# MD070B_DRIVER.net
KiCad netlist of a schematic drawn in Altium Designer
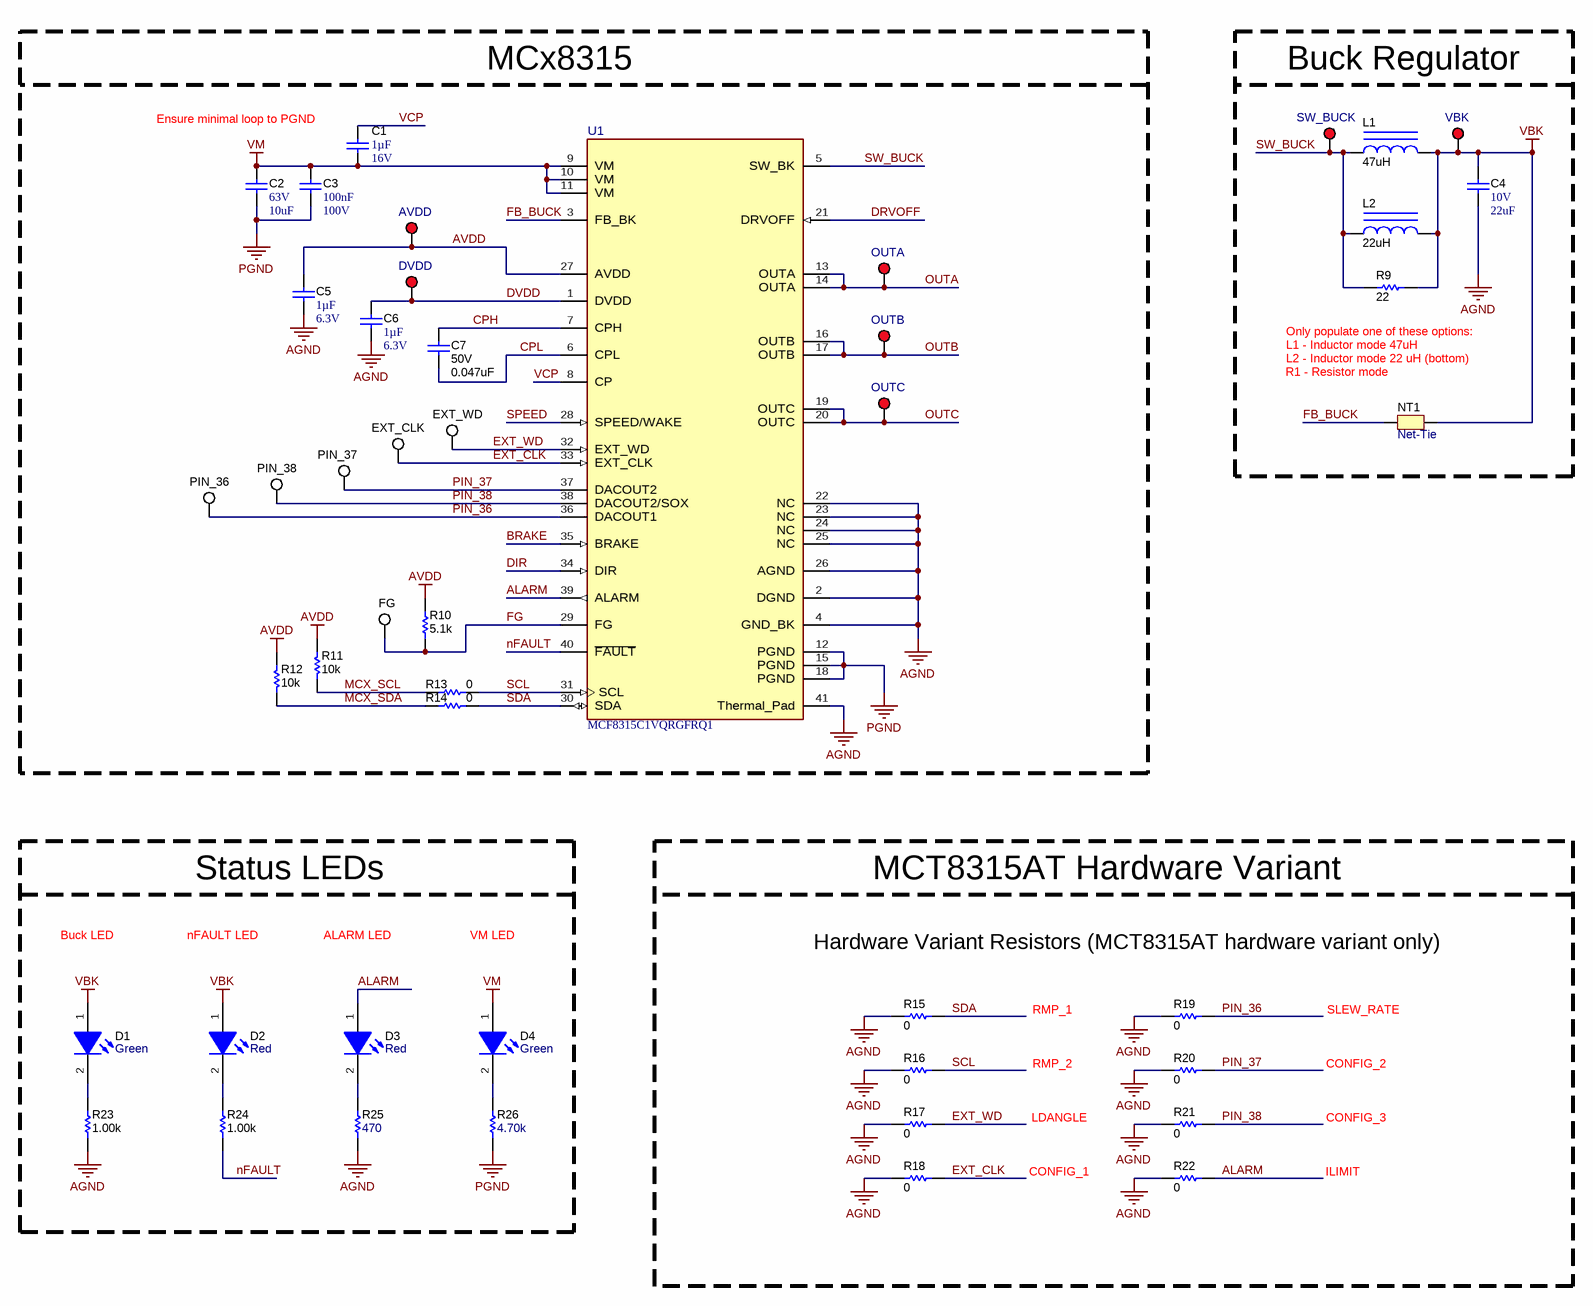
[diagram p0: MD070B_DRIVER.SchDoc]

(export (version "E")
  (design (tool "Eeschema 10.0.6"))
  (components
    (comp (ref "C1")
      (value "EMK107B7105KAHT")
      (footprint "0603L")
      (description "CAP, CERM, 1 µF, 16 V,+/- 10%, X7R, AEC-Q200 Grade 1, 0603")
      (fields
        (field (name "CAP_F") "1µF")
        (field (name "MANUFACTURER") "Taiyo Yuden")
        (field (name "VDC_V") "16V")
      )
      (libsource (lib "Altium Vault - TI") (part "Capacitor"))
    )
    (comp (ref "C2")
      (value "GRM32ER71J106KA12L")
      (footprint "1210_270L")
      (description "CAP, CERM, 10 uF, 63 V, +/- 10%, X7R, 1210")
      (fields
        (field (name "MANUFACTURER") "MuRata")
        (field (name "VDC_V") "63V")
        (field (name "VALUEDISPLAYED") "10uF")
        (field (name "PUBLISHER") "Texas Instruments")
      )
      (libsource (lib "Altium Vault - TI") (part "Capacitor"))
    )
    (comp (ref "C3")
      (value "GRM188R72A104KA35D")
      (footprint "0603")
      (description "CAP, CERM, 0.1 uF, 100 V, +/- 10%, X7R, 0603")
      (fields
        (field (name "CAP_F") "100nF")
        (field (name "MANUFACTURER") "MuRata")
        (field (name "VDC_V") "100V")
        (field (name "PUBLISHER") "Texas Instruments")
      )
      (libsource (lib "Altium Vault - TI") (part "Capacitor"))
    )
    (comp (ref "C4")
      (value "GRM31CR71A226KE15L")
      (footprint "1206_180L")
      (description "CAP, CERM, 22 uF, 10 V, +/- 10%, X7R, 1206")
      (fields
        (field (name "MANUFACTURER") "MuRata")
        (field (name "VDC_V") "10V")
        (field (name "VALUEDISPLAYED") "22uF")
        (field (name "PUBLISHER") "Texas Instruments")
      )
      (libsource (lib "Altium Vault - TI") (part "Capacitor"))
    )
    (comp (ref "C5")
      (value "C0603C105K9RACAUTO")
      (footprint "0603L")
      (description "CAP, CERM, 1 µF, 6.3 V,+/- 10%, X7R, AEC-Q200 Grade 1, 0603")
      (fields
        (field (name "CAP_F") "1µF")
        (field (name "MANUFACTURER") "Kemet")
        (field (name "VDC_V") "6.3V")
      )
      (libsource (lib "Altium Vault - TI") (part "Capacitor"))
    )
    (comp (ref "C6")
      (value "C0603C105K9RACAUTO")
      (footprint "0603L")
      (description "CAP, CERM, 1 µF, 6.3 V,+/- 10%, X7R, AEC-Q200 Grade 1, 0603")
      (fields
        (field (name "CAP_F") "1µF")
        (field (name "MANUFACTURER") "Kemet")
        (field (name "VDC_V") "6.3V")
      )
      (libsource (lib "Altium Vault - TI") (part "Capacitor"))
    )
    (comp (ref "C7")
      (value "C1005X7R1H473K050BB")
      (footprint "0402L")
      (description "CAP, CERM, 0.047 uF, 50 V, +/- 10%, X7R, 0402")
      (fields
        (field (name "MANUFACTURER") "TDK")
        (field (name "VDC_V") "50V")
        (field (name "VALUEDISPLAYED") "0.047uF")
        (field (name "PUBLISHER") "Texas Instruments")
      )
      (libsource (lib "Altium Vault - TI") (part "Capacitor"))
    )
    (comp (ref "D1")
      (value "Green")
      (footprint "LTST-C170KGKT_Green")
      (description "LED, Green, SMD")
      (fields (field (name "MANUFACTURER") "Lite-On") (field (name "PARTNUMBER") "LTST-C170KGKT"))
      (libsource (lib "Altium Vault - TI") (part "LED"))
    )
    (comp (ref "D2")
      (value "Red")
      (footprint "LED_LTST-C170_Red")
      (description "LED, Red, SMD")
      (fields (field (name "MANUFACTURER") "Lite-On") (field (name "PARTNUMBER") "LTST-C170KRKT"))
      (libsource (lib "Altium Vault - TI") (part "LED"))
    )
    (comp (ref "D3")
      (value "Red")
      (footprint "LED_LTST-C170_Red")
      (description "LED, Red, SMD")
      (fields (field (name "MANUFACTURER") "Lite-On") (field (name "PARTNUMBER") "LTST-C170KRKT"))
      (libsource (lib "Altium Vault - TI") (part "LED"))
    )
    (comp (ref "D4")
      (value "Green")
      (footprint "LTST-C170KGKT_Green")
      (description "LED, Green, SMD")
      (fields (field (name "MANUFACTURER") "Lite-On") (field (name "PARTNUMBER") "LTST-C170KGKT"))
      (libsource (lib "Altium Vault - TI") (part "LED"))
    )
    (comp (ref "L1")
      (value "78438335470")
      (footprint "WE-MAIA_3015")
      (description "Inductor, Shielded, Powdered Iron, 47 uH, 0.39 A, 2.3 ohm, AEC-Q200 Grade 1, SMD")
      (fields
        (field (name "MANUFACTURER") "Wurth Elektronik")
        (field (name "VALUEDISPLAYED") "47uH")
        (field (name "PUBLISHER") "Texas Instruments")
      )
      (libsource (lib "Altium Vault - TI") (part "Inductor_Iron"))
    )
    (comp (ref "L2")
      (value "78438335220")
      (footprint "WE-MAIA_3015")
      (description "Inductor, Shielded, Powdered Iron, 22 uH, 0.6 A, 1.04 ohm, AEC-Q200 Grade 1, SMD")
      (fields
        (field (name "MANUFACTURER") "Wurth Elektronik")
        (field (name "VALUEDISPLAYED") "22uH")
        (field (name "PUBLISHER") "Texas Instruments")
      )
      (libsource (lib "Altium Vault - TI") (part "Inductor_Iron"))
    )
    (comp (ref "NT1")
      (value "Net-Tie")
      (footprint "Net-Tie_10mil")
      (description "Single point connection between nets.")
      (libsource (lib "Altium Vault - TI") (part "Net-Tie"))
    )
    (comp (ref "R9")
      (value "CRCW251222R0JNEGHP")
      (footprint "2512")
      (description "RES, 22, 5%, 1.5 W, AEC-Q200 Grade 0, 2512")
      (fields (field (name "MANUFACTURER") "Vishay-Dale") (field (name "VALUEDISPLAYED") "22"))
      (libsource (lib "Altium Vault - TI") (part "Resistor"))
    )
    (comp (ref "R10")
      (value "CRCW06035K10JNEA")
      (footprint "0603L")
      (description "RES, 5.1 k, 5%, 0.1 W, AEC-Q200 Grade 0, 0603")
      (fields (field (name "MANUFACTURER") "Vishay-Dale") (field (name "VALUEDISPLAYED") "5.1k"))
      (libsource (lib "Altium Vault - TI") (part "Resistor"))
    )
    (comp (ref "R11")
      (value "CRCW060310K0JNEA")
      (footprint "0603")
      (description "RES, 10 k, 5%, 0.1 W, AEC-Q200 Grade 0, 0603")
      (fields (field (name "MANUFACTURER") "Vishay-Dale") (field (name "VALUEDISPLAYED") "10k"))
      (libsource (lib "Altium Vault - TI") (part "Resistor"))
    )
    (comp (ref "R12")
      (value "CRCW060310K0JNEA")
      (footprint "0603")
      (description "RES, 10 k, 5%, 0.1 W, AEC-Q200 Grade 0, 0603")
      (fields (field (name "MANUFACTURER") "Vishay-Dale") (field (name "VALUEDISPLAYED") "10k"))
      (libsource (lib "Altium Vault - TI") (part "Resistor"))
    )
    (comp (ref "R13")
      (value "ERJ-3GEY0R00V")
      (footprint "0603L")
      (description "RES, 0, 5%, 0.1 W, AEC-Q200 Grade 0, 0603")
      (fields (field (name "MANUFACTURER") "Panasonic") (field (name "VALUEDISPLAYED") "0"))
      (libsource (lib "Altium Vault - TI") (part "Resistor"))
    )
    (comp (ref "R14")
      (value "ERJ-3GEY0R00V")
      (footprint "0603L")
      (description "RES, 0, 5%, 0.1 W, AEC-Q200 Grade 0, 0603")
      (fields (field (name "MANUFACTURER") "Panasonic") (field (name "VALUEDISPLAYED") "0"))
      (libsource (lib "Altium Vault - TI") (part "Resistor"))
    )
    (comp (ref "R15")
      (value "ERJ-3GEY0R00V")
      (footprint "0603L")
      (description "RES, 0, 5%, 0.1 W, AEC-Q200 Grade 0, 0603")
      (fields (field (name "MANUFACTURER") "Panasonic") (field (name "VALUEDISPLAYED") "0"))
      (libsource (lib "Altium Vault - TI") (part "Resistor"))
    )
    (comp (ref "R16")
      (value "ERJ-3GEY0R00V")
      (footprint "0603L")
      (description "RES, 0, 5%, 0.1 W, AEC-Q200 Grade 0, 0603")
      (fields (field (name "MANUFACTURER") "Panasonic") (field (name "VALUEDISPLAYED") "0"))
      (libsource (lib "Altium Vault - TI") (part "Resistor"))
    )
    (comp (ref "R17")
      (value "ERJ-3GEY0R00V")
      (footprint "0603L")
      (description "RES, 0, 5%, 0.1 W, AEC-Q200 Grade 0, 0603")
      (fields (field (name "MANUFACTURER") "Panasonic") (field (name "VALUEDISPLAYED") "0"))
      (libsource (lib "Altium Vault - TI") (part "Resistor"))
    )
    (comp (ref "R18")
      (value "ERJ-3GEY0R00V")
      (footprint "0603L")
      (description "RES, 0, 5%, 0.1 W, AEC-Q200 Grade 0, 0603")
      (fields (field (name "MANUFACTURER") "Panasonic") (field (name "VALUEDISPLAYED") "0"))
      (libsource (lib "Altium Vault - TI") (part "Resistor"))
    )
    (comp (ref "R19")
      (value "ERJ-3GEY0R00V")
      (footprint "0603L")
      (description "RES, 0, 5%, 0.1 W, AEC-Q200 Grade 0, 0603")
      (fields (field (name "MANUFACTURER") "Panasonic") (field (name "VALUEDISPLAYED") "0"))
      (libsource (lib "Altium Vault - TI") (part "Resistor"))
    )
    (comp (ref "R20")
      (value "ERJ-3GEY0R00V")
      (footprint "0603L")
      (description "RES, 0, 5%, 0.1 W, AEC-Q200 Grade 0, 0603")
      (fields (field (name "MANUFACTURER") "Panasonic") (field (name "VALUEDISPLAYED") "0"))
      (libsource (lib "Altium Vault - TI") (part "Resistor"))
    )
    (comp (ref "R21")
      (value "ERJ-3GEY0R00V")
      (footprint "0603L")
      (description "RES, 0, 5%, 0.1 W, AEC-Q200 Grade 0, 0603")
      (fields (field (name "MANUFACTURER") "Panasonic") (field (name "VALUEDISPLAYED") "0"))
      (libsource (lib "Altium Vault - TI") (part "Resistor"))
    )
    (comp (ref "R22")
      (value "ERJ-3GEY0R00V")
      (footprint "0603L")
      (description "RES, 0, 5%, 0.1 W, AEC-Q200 Grade 0, 0603")
      (fields (field (name "MANUFACTURER") "Panasonic") (field (name "VALUEDISPLAYED") "0"))
      (libsource (lib "Altium Vault - TI") (part "Resistor"))
    )
    (comp (ref "R23")
      (value "RC0603FR-071KL")
      (footprint "0603")
      (description "RES, 1.00 k, 1%, 0.1 W, 0603")
      (fields (field (name "MANUFACTURER") "Yageo") (field (name "VALUEDISPLAYED") "1.00k"))
      (libsource (lib "Altium Vault - TI") (part "Resistor"))
    )
    (comp (ref "R24")
      (value "RC0603FR-071KL")
      (footprint "0603")
      (description "RES, 1.00 k, 1%, 0.1 W, 0603")
      (fields (field (name "MANUFACTURER") "Yageo") (field (name "VALUEDISPLAYED") "1.00k"))
      (libsource (lib "Altium Vault - TI") (part "Resistor"))
    )
    (comp (ref "R25")
      (value "RC0603JR-07470RL")
      (footprint "0603")
      (description "RES, 470, 5%, 0.1 W, 0603")
      (fields (field (name "MANUFACTURER") "Yageo") (field (name "VALUEDISPLAYED") "470"))
      (libsource (lib "Altium Vault - TI") (part "Resistor"))
    )
    (comp (ref "R26")
      (value "RT0603BRD074K7L")
      (footprint "0603L")
      (description "RES, 4.70 k, 0.1%, 0.1 W, 0603")
      (fields
        (field (name "MANUFACTURER") "Yageo America")
        (field (name "VALUEDISPLAYED") "4.70k")
        (field (name "PUBLISHER") "Texas Instruments")
      )
      (libsource (lib "Altium Vault - TI") (part "Resistor"))
    )
    (comp (ref "TP5")
      (value "SW_BUCK")
      (footprint "Keystone5000")
      (description "Test Point, Miniature, Red, TH")
      (fields
        (field (name "PARTNUMBER") "5000")
        (field (name "MANUFACTURER") "Keystone")
        (field (name "PUBLISHER") "Texas Instruments")
      )
      (libsource (lib "Altium Vault - TI") (part "CMP-0055137-1"))
    )
    (comp (ref "TP6")
      (value "VBK")
      (footprint "Keystone5000")
      (description "Test Point, Miniature, Red, TH")
      (fields
        (field (name "PARTNUMBER") "5000")
        (field (name "MANUFACTURER") "Keystone")
        (field (name "PUBLISHER") "Texas Instruments")
      )
      (libsource (lib "Altium Vault - TI") (part "CMP-0055137-1"))
    )
    (comp (ref "TP7")
      (value "AVDD")
      (footprint "Keystone5000")
      (description "Test Point, Miniature, Red, TH")
      (fields
        (field (name "PARTNUMBER") "5000")
        (field (name "MANUFACTURER") "Keystone")
        (field (name "PUBLISHER") "Texas Instruments")
      )
      (libsource (lib "Altium Vault - TI") (part "CMP-0055137-1"))
    )
    (comp (ref "TP8")
      (value "DVDD")
      (footprint "Keystone5000")
      (description "Test Point, Miniature, Red, TH")
      (fields
        (field (name "PARTNUMBER") "5000")
        (field (name "MANUFACTURER") "Keystone")
        (field (name "PUBLISHER") "Texas Instruments")
      )
      (libsource (lib "Altium Vault - TI") (part "CMP-0055137-1"))
    )
    (comp (ref "TP9")
      (value "OUTA")
      (footprint "Keystone5000")
      (description "Test Point, Miniature, Red, TH")
      (fields
        (field (name "PARTNUMBER") "5000")
        (field (name "MANUFACTURER") "Keystone")
        (field (name "PUBLISHER") "Texas Instruments")
      )
      (libsource (lib "Altium Vault - TI") (part "CMP-0055137-1"))
    )
    (comp (ref "TP10")
      (value "OUTB")
      (footprint "Keystone5000")
      (description "Test Point, Miniature, Red, TH")
      (fields
        (field (name "PARTNUMBER") "5000")
        (field (name "MANUFACTURER") "Keystone")
        (field (name "PUBLISHER") "Texas Instruments")
      )
      (libsource (lib "Altium Vault - TI") (part "CMP-0055137-1"))
    )
    (comp (ref "TP11")
      (value "OUTC")
      (footprint "Keystone5000")
      (description "Test Point, Miniature, Red, TH")
      (fields
        (field (name "PARTNUMBER") "5000")
        (field (name "MANUFACTURER") "Keystone")
        (field (name "PUBLISHER") "Texas Instruments")
      )
      (libsource (lib "Altium Vault - TI") (part "CMP-0055137-1"))
    )
    (comp (ref "TP12")
      (value "EXT_WD")
      (footprint "Keystone5002")
      (description "Test Point, Miniature, White, TH")
      (fields
        (field (name "MANUFACTURER") "Keystone")
        (field (name "PARTNUMBER") "5002")
        (field (name "PUBLISHER") "Texas Instruments")
      )
      (libsource (lib "Altium Vault - TI") (part "5002"))
    )
    (comp (ref "TP13")
      (value "EXT_CLK")
      (footprint "Keystone5002")
      (description "Test Point, Miniature, White, TH")
      (fields
        (field (name "MANUFACTURER") "Keystone")
        (field (name "PARTNUMBER") "5002")
        (field (name "PUBLISHER") "Texas Instruments")
      )
      (libsource (lib "Altium Vault - TI") (part "5002"))
    )
    (comp (ref "TP14")
      (value "PIN_37")
      (footprint "Keystone5002")
      (description "Test Point, Miniature, White, TH")
      (fields
        (field (name "MANUFACTURER") "Keystone")
        (field (name "PARTNUMBER") "5002")
        (field (name "PUBLISHER") "Texas Instruments")
      )
      (libsource (lib "Altium Vault - TI") (part "5002"))
    )
    (comp (ref "TP15")
      (value "PIN_38")
      (footprint "Keystone5002")
      (description "Test Point, Miniature, White, TH")
      (fields
        (field (name "MANUFACTURER") "Keystone")
        (field (name "PARTNUMBER") "5002")
        (field (name "PUBLISHER") "Texas Instruments")
      )
      (libsource (lib "Altium Vault - TI") (part "5002"))
    )
    (comp (ref "TP16")
      (value "PIN_36")
      (footprint "Keystone5002")
      (description "Test Point, Miniature, White, TH")
      (fields
        (field (name "MANUFACTURER") "Keystone")
        (field (name "PARTNUMBER") "5002")
        (field (name "PUBLISHER") "Texas Instruments")
      )
      (libsource (lib "Altium Vault - TI") (part "5002"))
    )
    (comp (ref "TP17")
      (value "FG")
      (footprint "Keystone5002")
      (description "Test Point, Miniature, White, TH")
      (fields
        (field (name "MANUFACTURER") "Keystone")
        (field (name "PARTNUMBER") "5002")
        (field (name "PUBLISHER") "Texas Instruments")
      )
      (libsource (lib "Altium Vault - TI") (part "5002"))
    )
    (comp (ref "U1")
      (value "MCF8315C1VQRGFRQ1")
      (footprint "RGF0040F-MFG")
      (description "Sensorless Field Oriented Control (FOC) Integrated FET BLDC Driver")
      (fields
        (field (name "MANUFACTURER") "Texas Instruments")
        (field (name "PARTNUMBER") "MCF8315C1VQRGFRQ1")
        (field (name "DIGIKEY PART NUMBER") "296-MCF8315C1VQRGFRQ1CT-ND")
      )
      (libsource (lib "Altium Vault - TI") (part "SYM-MCF8315C1VQRGFRQ1"))
    )
  )
  (nets
    (net (code "1") (name "/ALARM") (class "Default")
      (node (ref "D3") (pin "1") (pinfunction "A_1") (pintype "passive"))
      (node (ref "R22") (pin "1") (pinfunction "1_1") (pintype "passive"))
      (node (ref "U1") (pin "39") (pinfunction "ALARM_39") (pintype "output"))
    )
    (net (code "2") (name "/BRAKE") (class "Default")
      (node (ref "U1") (pin "35") (pinfunction "BRAKE_35") (pintype "input"))
    )
    (net (code "3") (name "/CPH") (class "Default")
      (node (ref "C7") (pin "1") (pinfunction "1_1") (pintype "passive"))
      (node (ref "U1") (pin "7") (pinfunction "CPH_7") (pintype "passive"))
    )
    (net (code "4") (name "/CPL") (class "Default")
      (node (ref "C7") (pin "2") (pinfunction "2_2") (pintype "passive"))
      (node (ref "U1") (pin "6") (pinfunction "CPL_6") (pintype "passive"))
    )
    (net (code "5") (name "/DIR") (class "Default")
      (node (ref "U1") (pin "34") (pinfunction "DIR_34") (pintype "input"))
    )
    (net (code "6") (name "/DRVOFF") (class "Default")
      (node (ref "U1") (pin "21") (pinfunction "DRVOFF_21") (pintype "input"))
    )
    (net (code "7") (name "/DVDD") (class "Default")
      (node (ref "C6") (pin "2") (pinfunction "2_2") (pintype "passive"))
      (node (ref "TP8") (pin "1") (pintype "passive"))
      (node (ref "U1") (pin "1") (pinfunction "DVDD_1") (pintype "power_in"))
    )
    (net (code "8") (name "/EXT_CLK") (class "Default")
      (node (ref "R18") (pin "1") (pinfunction "1_1") (pintype "passive"))
      (node (ref "TP13") (pin "1") (pintype "passive"))
      (node (ref "U1") (pin "33") (pinfunction "EXT_CLK_33") (pintype "input"))
    )
    (net (code "9") (name "/EXT_WD") (class "Default")
      (node (ref "R17") (pin "1") (pinfunction "1_1") (pintype "passive"))
      (node (ref "TP12") (pin "1") (pintype "passive"))
      (node (ref "U1") (pin "32") (pinfunction "EXT_WD_32") (pintype "input"))
    )
    (net (code "10") (name "/FB_BUCK") (class "Default")
      (node (ref "NT1") (pin "1") (pinfunction "1_1") (pintype "passive"))
      (node (ref "U1") (pin "3") (pinfunction "FB_BK_3") (pintype "power_in"))
    )
    (net (code "11") (name "/FG") (class "Default")
      (node (ref "R10") (pin "1") (pinfunction "1_1") (pintype "passive"))
      (node (ref "TP17") (pin "1") (pintype "passive"))
      (node (ref "U1") (pin "29") (pinfunction "FG_29") (pintype "open_collector"))
    )
    (net (code "12") (name "/MCX_SCL") (class "Default")
      (node (ref "R11") (pin "2") (pinfunction "2_2") (pintype "passive"))
      (node (ref "R13") (pin "1") (pinfunction "1_1") (pintype "passive"))
    )
    (net (code "13") (name "/MCX_SDA") (class "Default")
      (node (ref "R12") (pin "2") (pinfunction "2_2") (pintype "passive"))
      (node (ref "R14") (pin "1") (pinfunction "1_1") (pintype "passive"))
    )
    (net (code "14") (name "/OUTA") (class "Default")
      (node (ref "TP9") (pin "1") (pintype "passive"))
      (node (ref "U1") (pin "13") (pinfunction "OUTA_13") (pintype "passive"))
      (node (ref "U1") (pin "14") (pinfunction "OUTA_14") (pintype "passive"))
    )
    (net (code "15") (name "/OUTB") (class "Default")
      (node (ref "TP10") (pin "1") (pintype "passive"))
      (node (ref "U1") (pin "16") (pinfunction "OUTB_16") (pintype "passive"))
      (node (ref "U1") (pin "17") (pinfunction "OUTB_17") (pintype "passive"))
    )
    (net (code "16") (name "/OUTC") (class "Default")
      (node (ref "TP11") (pin "1") (pintype "passive"))
      (node (ref "U1") (pin "19") (pinfunction "OUTC_19") (pintype "passive"))
      (node (ref "U1") (pin "20") (pinfunction "OUTC_20") (pintype "passive"))
    )
    (net (code "17") (name "/PIN_36") (class "Default")
      (node (ref "R19") (pin "1") (pinfunction "1_1") (pintype "passive"))
      (node (ref "TP16") (pin "1") (pintype "passive"))
      (node (ref "U1") (pin "36") (pinfunction "DACOUT1_36") (pintype "passive"))
    )
    (net (code "18") (name "/PIN_37") (class "Default")
      (node (ref "R20") (pin "1") (pinfunction "1_1") (pintype "passive"))
      (node (ref "TP14") (pin "1") (pintype "passive"))
      (node (ref "U1") (pin "37") (pinfunction "DACOUT2_37") (pintype "passive"))
    )
    (net (code "19") (name "/PIN_38") (class "Default")
      (node (ref "R21") (pin "1") (pinfunction "1_1") (pintype "passive"))
      (node (ref "TP15") (pin "1") (pintype "passive"))
      (node (ref "U1") (pin "38") (pinfunction "DACOUT2/SOX_38") (pintype "passive"))
    )
    (net (code "20") (name "/SCL") (class "Default")
      (node (ref "R13") (pin "2") (pinfunction "2_2") (pintype "passive"))
      (node (ref "R16") (pin "1") (pinfunction "1_1") (pintype "passive"))
      (node (ref "U1") (pin "31") (pinfunction "SCL_31") (pintype "input"))
    )
    (net (code "21") (name "/SDA") (class "Default")
      (node (ref "R14") (pin "2") (pinfunction "2_2") (pintype "passive"))
      (node (ref "R15") (pin "1") (pinfunction "1_1") (pintype "passive"))
      (node (ref "U1") (pin "30") (pinfunction "SDA_30") (pintype "bidirectional"))
    )
    (net (code "22") (name "/SPEED") (class "Default")
      (node (ref "U1") (pin "28") (pinfunction "SPEED/WAKE_28") (pintype "input"))
    )
    (net (code "23") (name "/SW_BUCK") (class "Default")
      (node (ref "L1") (pin "1") (pinfunction "1_1") (pintype "passive"))
      (node (ref "L2") (pin "1") (pinfunction "1_1") (pintype "passive"))
      (node (ref "R9") (pin "1") (pinfunction "1_1") (pintype "passive"))
      (node (ref "TP5") (pin "1") (pintype "passive"))
      (node (ref "U1") (pin "5") (pinfunction "SW_BK_5") (pintype "power_in"))
    )
    (net (code "24") (name "/VCP") (class "Default")
      (node (ref "C1") (pin "1") (pinfunction "1_1") (pintype "passive"))
      (node (ref "U1") (pin "8") (pinfunction "CP_8") (pintype "passive"))
    )
    (net (code "25") (name "/nFAULT") (class "Default")
      (node (ref "R24") (pin "1") (pinfunction "1_1") (pintype "passive"))
      (node (ref "U1") (pin "40") (pinfunction "~{FAULT}_40") (pintype "open_collector"))
    )
    (net (code "26") (name "AGND") (class "Default")
      (node (ref "C4") (pin "2") (pinfunction "2_2") (pintype "passive"))
      (node (ref "C5") (pin "1") (pinfunction "1_1") (pintype "passive"))
      (node (ref "C6") (pin "1") (pinfunction "1_1") (pintype "passive"))
      (node (ref "R15") (pin "2") (pinfunction "2_2") (pintype "passive"))
      (node (ref "R16") (pin "2") (pinfunction "2_2") (pintype "passive"))
      (node (ref "R17") (pin "2") (pinfunction "2_2") (pintype "passive"))
      (node (ref "R18") (pin "2") (pinfunction "2_2") (pintype "passive"))
      (node (ref "R19") (pin "2") (pinfunction "2_2") (pintype "passive"))
      (node (ref "R20") (pin "2") (pinfunction "2_2") (pintype "passive"))
      (node (ref "R21") (pin "2") (pinfunction "2_2") (pintype "passive"))
      (node (ref "R22") (pin "2") (pinfunction "2_2") (pintype "passive"))
      (node (ref "R23") (pin "1") (pinfunction "1_1") (pintype "passive"))
      (node (ref "R25") (pin "1") (pinfunction "1_1") (pintype "passive"))
      (node (ref "U1") (pin "2") (pinfunction "DGND_2") (pintype "power_in"))
      (node (ref "U1") (pin "22") (pinfunction "NC_22") (pintype "passive"))
      (node (ref "U1") (pin "23") (pinfunction "NC_23") (pintype "passive"))
      (node (ref "U1") (pin "24") (pinfunction "NC_24") (pintype "passive"))
      (node (ref "U1") (pin "25") (pinfunction "NC_25") (pintype "passive"))
      (node (ref "U1") (pin "26") (pinfunction "AGND_26") (pintype "power_in"))
      (node (ref "U1") (pin "4") (pinfunction "GND_BK_4") (pintype "power_in"))
      (node (ref "U1") (pin "41") (pinfunction "Thermal_Pad_41") (pintype "power_in"))
    )
    (net (code "27") (name "AVDD") (class "Default")
      (node (ref "C5") (pin "2") (pinfunction "2_2") (pintype "passive"))
      (node (ref "R10") (pin "2") (pinfunction "2_2") (pintype "passive"))
      (node (ref "R11") (pin "1") (pinfunction "1_1") (pintype "passive"))
      (node (ref "R12") (pin "1") (pinfunction "1_1") (pintype "passive"))
      (node (ref "TP7") (pin "1") (pintype "passive"))
      (node (ref "U1") (pin "27") (pinfunction "AVDD_27") (pintype "power_in"))
    )
    (net (code "28") (name "Net-(D1-K)") (class "Default")
      (node (ref "D1") (pin "2") (pinfunction "K_2") (pintype "passive"))
      (node (ref "R23") (pin "2") (pinfunction "2_2") (pintype "passive"))
    )
    (net (code "29") (name "Net-(D2-K)") (class "Default")
      (node (ref "D2") (pin "2") (pinfunction "K_2") (pintype "passive"))
      (node (ref "R24") (pin "2") (pinfunction "2_2") (pintype "passive"))
    )
    (net (code "30") (name "Net-(D3-K)") (class "Default")
      (node (ref "D3") (pin "2") (pinfunction "K_2") (pintype "passive"))
      (node (ref "R25") (pin "2") (pinfunction "2_2") (pintype "passive"))
    )
    (net (code "31") (name "Net-(D4-K)") (class "Default")
      (node (ref "D4") (pin "2") (pinfunction "K_2") (pintype "passive"))
      (node (ref "R26") (pin "2") (pinfunction "2_2") (pintype "passive"))
    )
    (net (code "32") (name "PGND") (class "Default")
      (node (ref "C2") (pin "2") (pinfunction "2_2") (pintype "passive"))
      (node (ref "C3") (pin "2") (pinfunction "2_2") (pintype "passive"))
      (node (ref "R26") (pin "1") (pinfunction "1_1") (pintype "passive"))
      (node (ref "U1") (pin "12") (pinfunction "PGND_12") (pintype "power_in"))
      (node (ref "U1") (pin "15") (pinfunction "PGND_15") (pintype "power_in"))
      (node (ref "U1") (pin "18") (pinfunction "PGND_18") (pintype "power_in"))
    )
    (net (code "33") (name "VBK") (class "Default")
      (node (ref "C4") (pin "1") (pinfunction "1_1") (pintype "passive"))
      (node (ref "D1") (pin "1") (pinfunction "A_1") (pintype "passive"))
      (node (ref "D2") (pin "1") (pinfunction "A_1") (pintype "passive"))
      (node (ref "L1") (pin "2") (pinfunction "2_2") (pintype "passive"))
      (node (ref "L2") (pin "2") (pinfunction "2_2") (pintype "passive"))
      (node (ref "NT1") (pin "2") (pinfunction "2_2") (pintype "passive"))
      (node (ref "R9") (pin "2") (pinfunction "2_2") (pintype "passive"))
      (node (ref "TP6") (pin "1") (pintype "passive"))
    )
    (net (code "34") (name "VM") (class "Default")
      (node (ref "C1") (pin "2") (pinfunction "2_2") (pintype "passive"))
      (node (ref "C2") (pin "1") (pinfunction "1_1") (pintype "passive"))
      (node (ref "C3") (pin "1") (pinfunction "1_1") (pintype "passive"))
      (node (ref "D4") (pin "1") (pinfunction "A_1") (pintype "passive"))
      (node (ref "U1") (pin "10") (pinfunction "VM_10") (pintype "power_in"))
      (node (ref "U1") (pin "11") (pinfunction "VM_11") (pintype "power_in"))
      (node (ref "U1") (pin "9") (pinfunction "VM_9") (pintype "power_in"))
    )
  )
)
